# VCF-LM324-Stereo.net
KiCad netlist of a schematic drawn in EAGLE
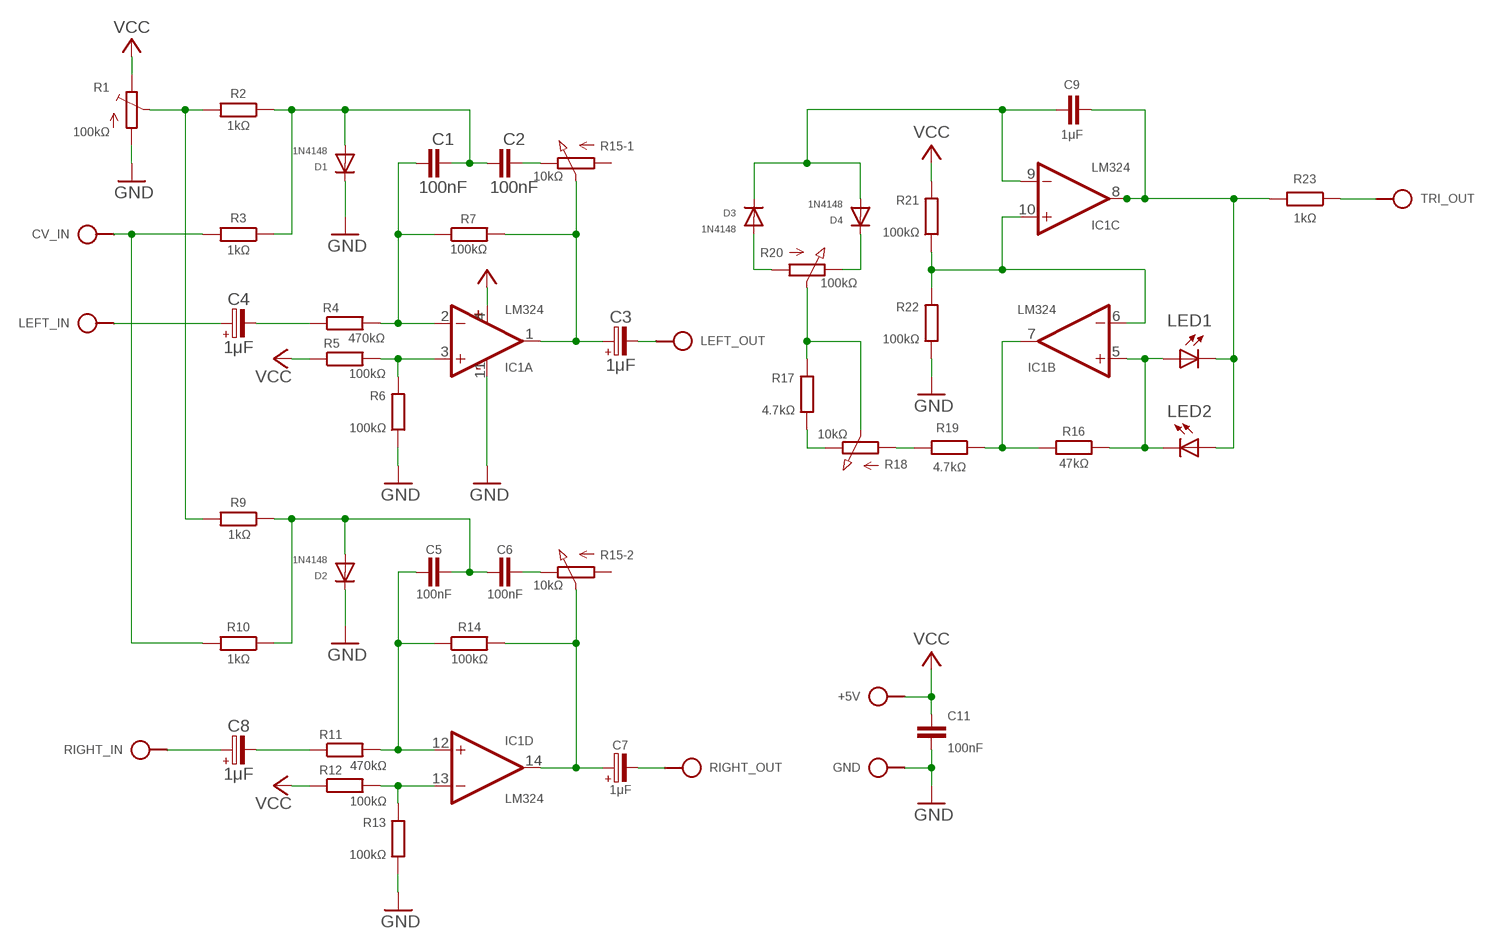
[diagram p0: schematic, sheet 1]

(export (version "E")
  (design (tool "Eeschema 10.0.6"))
  (components
    (comp (ref "+5V")
      (value "VCC")
      (footprint "eagle-import:SPAD")
      (libsource (lib "eagle-import") (part "SPAD"))
    )
    (comp (ref "C1")
      (value "100nF")
      (footprint "eagle-import:C050-024X044")
      (libsource (lib "eagle-import") (part "C050-024X044"))
    )
    (comp (ref "C2")
      (value "100nF")
      (footprint "eagle-import:C050-024X044")
      (libsource (lib "eagle-import") (part "C050-024X044"))
    )
    (comp (ref "C3")
      (value "1μF")
      (footprint "eagle-import:E2,5-3")
      (libsource (lib "eagle-import") (part "CPOLE2,5-3"))
    )
    (comp (ref "C4")
      (value "1μF")
      (footprint "eagle-import:E2,5-3")
      (libsource (lib "eagle-import") (part "CPOLE2,5-3"))
    )
    (comp (ref "C5")
      (value "100nF")
      (footprint "eagle-import:C050-024X044")
      (libsource (lib "eagle-import") (part "C050-024X044"))
    )
    (comp (ref "C6")
      (value "100nF")
      (footprint "eagle-import:C050-024X044")
      (libsource (lib "eagle-import") (part "C050-024X044"))
    )
    (comp (ref "C7")
      (value "1μF")
      (footprint "eagle-import:E2,5-3")
      (libsource (lib "eagle-import") (part "CPOLE2,5-3"))
    )
    (comp (ref "C8")
      (value "1μF")
      (footprint "eagle-import:E2,5-3")
      (libsource (lib "eagle-import") (part "CPOLE2,5-3"))
    )
    (comp (ref "C9")
      (value "1μF")
      (footprint "eagle-import:C050-024X044_V")
      (libsource (lib "eagle-import") (part "C050-024X044/V"))
    )
    (comp (ref "C11")
      (value "100nF")
      (footprint "eagle-import:C050-020X036")
      (libsource (lib "eagle-import") (part "C050-020X036"))
    )
    (comp (ref "CV_IN")
      (value "CV_IN")
      (footprint "eagle-import:SPAD")
      (libsource (lib "eagle-import") (part "SPAD"))
    )
    (comp (ref "D1")
      (value "1N4148")
      (footprint "eagle-import:DO34-10V")
      (libsource (lib "eagle-import") (part "1N414834-10V"))
    )
    (comp (ref "D2")
      (value "1N4148")
      (footprint "eagle-import:DO34-7V")
      (libsource (lib "eagle-import") (part "1N414834-7V"))
    )
    (comp (ref "D3")
      (value "1N4148")
      (footprint "eagle-import:DO34-7V")
      (libsource (lib "eagle-import") (part "1N414834-7V"))
    )
    (comp (ref "D4")
      (value "1N4148")
      (footprint "eagle-import:DO34-7V")
      (libsource (lib "eagle-import") (part "1N414834-7V"))
    )
    (comp (ref "GND")
      (value "GND")
      (footprint "eagle-import:SPAD")
      (libsource (lib "eagle-import") (part "SPAD"))
    )
    (comp (ref "IC1")
      (value "LM324")
      (footprint "eagle-import:DIL14")
      (libsource (lib "eagle-import") (part "LM324N"))
    )
    (comp (ref "LED1")
      (value "LED3MM")
      (footprint "eagle-import:LED3MM")
      (libsource (lib "eagle-import") (part "LED3MM"))
    )
    (comp (ref "LED2")
      (value "LED3MM")
      (footprint "eagle-import:LED3MM")
      (libsource (lib "eagle-import") (part "LED3MM"))
    )
    (comp (ref "LEFT_IN")
      (value "AUDIO_IN")
      (footprint "eagle-import:SPAD")
      (libsource (lib "eagle-import") (part "SPAD"))
    )
    (comp (ref "LEFT_OUT")
      (value "AUDIO_OUT")
      (footprint "eagle-import:SPAD")
      (libsource (lib "eagle-import") (part "SPAD"))
    )
    (comp (ref "R1")
      (value "100kΩ")
      (footprint "eagle-import:B64Y")
      (libsource (lib "eagle-import") (part "TRIM"))
    )
    (comp (ref "R2")
      (value "1kΩ")
      (footprint "eagle-import:0202_7")
      (libsource (lib "eagle-import") (part "R0202/7"))
    )
    (comp (ref "R3")
      (value "1kΩ")
      (footprint "eagle-import:0202_7")
      (libsource (lib "eagle-import") (part "R0202/7"))
    )
    (comp (ref "R4")
      (value "470kΩ")
      (footprint "eagle-import:0202_7")
      (libsource (lib "eagle-import") (part "R0202/7"))
    )
    (comp (ref "R5")
      (value "100kΩ")
      (footprint "eagle-import:0202_7")
      (libsource (lib "eagle-import") (part "R0202/7"))
    )
    (comp (ref "R6")
      (value "100kΩ")
      (footprint "eagle-import:0202_7")
      (libsource (lib "eagle-import") (part "R0202/7"))
    )
    (comp (ref "R7")
      (value "100kΩ")
      (footprint "eagle-import:0202_7")
      (libsource (lib "eagle-import") (part "R0202/7"))
    )
    (comp (ref "R9")
      (value "1kΩ")
      (footprint "eagle-import:0202_10")
      (libsource (lib "eagle-import") (part "R0202/10"))
    )
    (comp (ref "R10")
      (value "1kΩ")
      (footprint "eagle-import:0202_10")
      (libsource (lib "eagle-import") (part "R0202/10"))
    )
    (comp (ref "R11")
      (value "470kΩ")
      (footprint "eagle-import:0202_7")
      (libsource (lib "eagle-import") (part "R0202/7"))
    )
    (comp (ref "R12")
      (value "100kΩ")
      (footprint "eagle-import:0202_7")
      (libsource (lib "eagle-import") (part "R0202/7"))
    )
    (comp (ref "R13")
      (value "100kΩ")
      (footprint "eagle-import:0202_7")
      (libsource (lib "eagle-import") (part "R0202/7"))
    )
    (comp (ref "R14")
      (value "100kΩ")
      (footprint "eagle-import:0202_7")
      (libsource (lib "eagle-import") (part "R0202/7"))
    )
    (comp (ref "R15")
      (value "10kΩ")
      (footprint "eagle-import:POT-STEREO-2X3")
      (libsource (lib "eagle-import") (part "POT-STEREO"))
    )
    (comp (ref "R16")
      (value "47kΩ")
      (footprint "eagle-import:0202_7-V")
      (libsource (lib "eagle-import") (part "R0202/7-V"))
    )
    (comp (ref "R17")
      (value "4.7kΩ")
      (footprint "eagle-import:0202_7")
      (libsource (lib "eagle-import") (part "R0202/7"))
    )
    (comp (ref "R18")
      (value "10kΩ")
      (footprint "eagle-import:POT")
      (libsource (lib "eagle-import") (part "POT"))
    )
    (comp (ref "R19")
      (value "4.7kΩ")
      (footprint "eagle-import:0202_7-V")
      (libsource (lib "eagle-import") (part "R0202/7-V"))
    )
    (comp (ref "R20")
      (value "100kΩ")
      (footprint "eagle-import:POT")
      (libsource (lib "eagle-import") (part "POT"))
    )
    (comp (ref "R21")
      (value "100kΩ")
      (footprint "eagle-import:0202_7-V")
      (libsource (lib "eagle-import") (part "R0202/7-V"))
    )
    (comp (ref "R22")
      (value "100kΩ")
      (footprint "eagle-import:0202_7-V")
      (libsource (lib "eagle-import") (part "R0202/7-V"))
    )
    (comp (ref "R23")
      (value "1kΩ")
      (footprint "eagle-import:0202_7-V")
      (libsource (lib "eagle-import") (part "R0202/7-V"))
    )
    (comp (ref "RIGHT_IN")
      (value "AUDIO_IN")
      (footprint "eagle-import:SPAD")
      (libsource (lib "eagle-import") (part "SPAD"))
    )
    (comp (ref "RIGHT_OUT")
      (value "AUDIO_OUT")
      (footprint "eagle-import:SPAD")
      (libsource (lib "eagle-import") (part "SPAD"))
    )
    (comp (ref "TRI_OUT")
      (value "TRIANGLE")
      (footprint "eagle-import:SPAD")
      (libsource (lib "eagle-import") (part "SPAD"))
    )
  )
  (nets
    (net (code "1") (name "GND") (class "Default")
      (node (ref "C11") (pin "2") (pinfunction "2_2") (pintype "passive"))
      (node (ref "D1") (pin "C") (pinfunction "C_C") (pintype "passive"))
      (node (ref "D2") (pin "C") (pinfunction "C_C") (pintype "passive"))
      (node (ref "GND") (pin "1") (pinfunction "P$1_1") (pintype "bidirectional"))
      (node (ref "IC1") (pin "11") (pinfunction "V-_11") (pintype "power_in"))
      (node (ref "R1") (pin "A") (pinfunction "A_A") (pintype "passive"))
      (node (ref "R13") (pin "1") (pinfunction "1_1") (pintype "passive"))
      (node (ref "R22") (pin "1") (pinfunction "1_1") (pintype "passive"))
      (node (ref "R6") (pin "1") (pinfunction "1_1") (pintype "passive"))
    )
    (net (code "2") (name "Net-(C1-Pad2)") (class "Default")
      (node (ref "C1") (pin "2") (pinfunction "2_2") (pintype "passive"))
      (node (ref "C2") (pin "1") (pinfunction "1_1") (pintype "passive"))
      (node (ref "D1") (pin "A") (pinfunction "A_A") (pintype "passive"))
      (node (ref "R2") (pin "1") (pinfunction "1_1") (pintype "passive"))
      (node (ref "R3") (pin "1") (pinfunction "1_1") (pintype "passive"))
    )
    (net (code "3") (name "Net-(C4-Pad-)") (class "Default")
      (node (ref "C4") (pin "-") (pinfunction "-_-") (pintype "passive"))
      (node (ref "R4") (pin "1") (pinfunction "1_1") (pintype "passive"))
    )
    (net (code "4") (name "Net-(C5-Pad2)") (class "Default")
      (node (ref "C5") (pin "2") (pinfunction "2_2") (pintype "passive"))
      (node (ref "C6") (pin "1") (pinfunction "1_1") (pintype "passive"))
      (node (ref "D2") (pin "A") (pinfunction "A_A") (pintype "passive"))
      (node (ref "R10") (pin "1") (pinfunction "1_1") (pintype "passive"))
      (node (ref "R9") (pin "1") (pinfunction "1_1") (pintype "passive"))
    )
    (net (code "5") (name "Net-(C8-Pad-)") (class "Default")
      (node (ref "C8") (pin "-") (pinfunction "-_-") (pintype "passive"))
      (node (ref "R11") (pin "1") (pinfunction "1_1") (pintype "passive"))
    )
    (net (code "6") (name "Net-(CV_IN-P$1)") (class "Default")
      (node (ref "CV_IN") (pin "1") (pinfunction "P$1_1") (pintype "bidirectional"))
      (node (ref "R10") (pin "2") (pinfunction "2_2") (pintype "passive"))
      (node (ref "R3") (pin "2") (pinfunction "2_2") (pintype "passive"))
    )
    (net (code "7") (name "Net-(IC1A-+IN)") (class "Default")
      (node (ref "IC1") (pin "3") (pinfunction "+IN_3") (pintype "input"))
      (node (ref "R5") (pin "2") (pinfunction "2_2") (pintype "passive"))
      (node (ref "R6") (pin "2") (pinfunction "2_2") (pintype "passive"))
    )
    (net (code "8") (name "Net-(IC1A--IN)") (class "Default")
      (node (ref "C1") (pin "1") (pinfunction "1_1") (pintype "passive"))
      (node (ref "IC1") (pin "2") (pinfunction "-IN_2") (pintype "input"))
      (node (ref "R4") (pin "2") (pinfunction "2_2") (pintype "passive"))
      (node (ref "R7") (pin "1") (pinfunction "1_1") (pintype "passive"))
    )
    (net (code "9") (name "Net-(IC1A-OUT)") (class "Default")
      (node (ref "C3") (pin "+") (pinfunction "+_+") (pintype "passive"))
      (node (ref "IC1") (pin "1") (pinfunction "OUT_1") (pintype "output"))
      (node (ref "R15") (pin "1-S") (pinfunction "S_1-S") (pintype "passive"))
      (node (ref "R7") (pin "2") (pinfunction "2_2") (pintype "passive"))
    )
    (net (code "10") (name "Net-(IC1B-+IN)") (class "Default")
      (node (ref "IC1") (pin "5") (pinfunction "+IN_5") (pintype "input"))
      (node (ref "LED1") (pin "A") (pinfunction "A_A") (pintype "passive"))
      (node (ref "LED2") (pin "K") (pinfunction "C_K") (pintype "passive"))
      (node (ref "R16") (pin "1") (pinfunction "1_1") (pintype "passive"))
    )
    (net (code "11") (name "Net-(IC1B--IN)") (class "Default")
      (node (ref "IC1") (pin "10") (pinfunction "+IN_10") (pintype "input"))
      (node (ref "IC1") (pin "6") (pinfunction "-IN_6") (pintype "input"))
      (node (ref "R21") (pin "1") (pinfunction "1_1") (pintype "passive"))
      (node (ref "R22") (pin "2") (pinfunction "2_2") (pintype "passive"))
    )
    (net (code "12") (name "Net-(IC1B-OUT)") (class "Default")
      (node (ref "IC1") (pin "7") (pinfunction "OUT_7") (pintype "output"))
      (node (ref "R16") (pin "2") (pinfunction "2_2") (pintype "passive"))
      (node (ref "R19") (pin "1") (pinfunction "1_1") (pintype "passive"))
    )
    (net (code "13") (name "Net-(IC1C--IN)") (class "Default")
      (node (ref "C9") (pin "1") (pinfunction "1_1") (pintype "passive"))
      (node (ref "D3") (pin "C") (pinfunction "C_C") (pintype "passive"))
      (node (ref "D4") (pin "A") (pinfunction "A_A") (pintype "passive"))
      (node (ref "IC1") (pin "9") (pinfunction "-IN_9") (pintype "input"))
    )
    (net (code "14") (name "Net-(IC1C-OUT)") (class "Default")
      (node (ref "C9") (pin "2") (pinfunction "2_2") (pintype "passive"))
      (node (ref "IC1") (pin "8") (pinfunction "OUT_8") (pintype "output"))
      (node (ref "LED1") (pin "K") (pinfunction "C_K") (pintype "passive"))
      (node (ref "LED2") (pin "A") (pinfunction "A_A") (pintype "passive"))
      (node (ref "R23") (pin "2") (pinfunction "2_2") (pintype "passive"))
    )
    (net (code "15") (name "Net-(IC1D-+IN)") (class "Default")
      (node (ref "C5") (pin "1") (pinfunction "1_1") (pintype "passive"))
      (node (ref "IC1") (pin "12") (pinfunction "+IN_12") (pintype "input"))
      (node (ref "R11") (pin "2") (pinfunction "2_2") (pintype "passive"))
      (node (ref "R14") (pin "1") (pinfunction "1_1") (pintype "passive"))
    )
    (net (code "16") (name "Net-(IC1D--IN)") (class "Default")
      (node (ref "IC1") (pin "13") (pinfunction "-IN_13") (pintype "input"))
      (node (ref "R12") (pin "2") (pinfunction "2_2") (pintype "passive"))
      (node (ref "R13") (pin "2") (pinfunction "2_2") (pintype "passive"))
    )
    (net (code "17") (name "Net-(IC1D-OUT)") (class "Default")
      (node (ref "C7") (pin "+") (pinfunction "+_+") (pintype "passive"))
      (node (ref "IC1") (pin "14") (pinfunction "OUT_14") (pintype "output"))
      (node (ref "R14") (pin "2") (pinfunction "2_2") (pintype "passive"))
      (node (ref "R15") (pin "2-S") (pinfunction "S_2-S") (pintype "passive"))
    )
    (net (code "18") (name "Net-(LEFT_IN-P$1)") (class "Default")
      (node (ref "C4") (pin "+") (pinfunction "+_+") (pintype "passive"))
      (node (ref "LEFT_IN") (pin "1") (pinfunction "P$1_1") (pintype "bidirectional"))
    )
    (net (code "19") (name "Net-(LEFT_OUT-P$1)") (class "Default")
      (node (ref "C3") (pin "-") (pinfunction "-_-") (pintype "passive"))
      (node (ref "LEFT_OUT") (pin "1") (pinfunction "P$1_1") (pintype "bidirectional"))
    )
    (net (code "20") (name "Net-(R1-PadS)") (class "Default")
      (node (ref "R1") (pin "S") (pinfunction "S_S") (pintype "passive"))
      (node (ref "R2") (pin "2") (pinfunction "2_2") (pintype "passive"))
      (node (ref "R9") (pin "2") (pinfunction "2_2") (pintype "passive"))
    )
    (net (code "21") (name "Net-(R15A-E)") (class "Default")
      (node (ref "C2") (pin "2") (pinfunction "2_2") (pintype "passive"))
      (node (ref "R15") (pin "1-E") (pinfunction "E_1-E") (pintype "passive"))
    )
    (net (code "22") (name "Net-(R15B-E)") (class "Default")
      (node (ref "C6") (pin "2") (pinfunction "2_2") (pintype "passive"))
      (node (ref "R15") (pin "2-E") (pinfunction "E_2-E") (pintype "passive"))
    )
    (net (code "23") (name "Net-(R18-A)") (class "Default")
      (node (ref "R18") (pin "1") (pinfunction "A_1") (pintype "passive"))
      (node (ref "R19") (pin "2") (pinfunction "2_2") (pintype "passive"))
    )
    (net (code "24") (name "Net-(R18-E)") (class "Default")
      (node (ref "R17") (pin "1") (pinfunction "1_1") (pintype "passive"))
      (node (ref "R18") (pin "3") (pinfunction "E_3") (pintype "passive"))
    )
    (net (code "25") (name "Net-(R18-S)") (class "Default")
      (node (ref "R17") (pin "2") (pinfunction "2_2") (pintype "passive"))
      (node (ref "R18") (pin "2") (pinfunction "S_2") (pintype "passive"))
      (node (ref "R20") (pin "2") (pinfunction "S_2") (pintype "passive"))
    )
    (net (code "26") (name "Net-(R20-A)") (class "Default")
      (node (ref "D3") (pin "A") (pinfunction "A_A") (pintype "passive"))
      (node (ref "R20") (pin "1") (pinfunction "A_1") (pintype "passive"))
    )
    (net (code "27") (name "Net-(R20-E)") (class "Default")
      (node (ref "D4") (pin "C") (pinfunction "C_C") (pintype "passive"))
      (node (ref "R20") (pin "3") (pinfunction "E_3") (pintype "passive"))
    )
    (net (code "28") (name "Net-(RIGHT_IN-P$1)") (class "Default")
      (node (ref "C8") (pin "+") (pinfunction "+_+") (pintype "passive"))
      (node (ref "RIGHT_IN") (pin "1") (pinfunction "P$1_1") (pintype "bidirectional"))
    )
    (net (code "29") (name "Net-(RIGHT_OUT-P$1)") (class "Default")
      (node (ref "C7") (pin "-") (pinfunction "-_-") (pintype "passive"))
      (node (ref "RIGHT_OUT") (pin "1") (pinfunction "P$1_1") (pintype "bidirectional"))
    )
    (net (code "30") (name "Net-(TRI_OUT-P$1)") (class "Default")
      (node (ref "R23") (pin "1") (pinfunction "1_1") (pintype "passive"))
      (node (ref "TRI_OUT") (pin "1") (pinfunction "P$1_1") (pintype "bidirectional"))
    )
    (net (code "31") (name "VCC") (class "Default")
      (node (ref "+5V") (pin "1") (pinfunction "P$1_1") (pintype "bidirectional"))
      (node (ref "C11") (pin "1") (pinfunction "1_1") (pintype "passive"))
      (node (ref "IC1") (pin "4") (pinfunction "V+_4") (pintype "power_in"))
      (node (ref "R1") (pin "E") (pinfunction "E_E") (pintype "passive"))
      (node (ref "R12") (pin "1") (pinfunction "1_1") (pintype "passive"))
      (node (ref "R21") (pin "2") (pinfunction "2_2") (pintype "passive"))
      (node (ref "R5") (pin "1") (pinfunction "1_1") (pintype "passive"))
    )
    (net (code "32") (name "unconnected-(R15A-A-Pad1-A)") (class "Default")
      (node (ref "R15") (pin "1-A") (pinfunction "A_1-A") (pintype "passive"))
    )
    (net (code "33") (name "unconnected-(R15B-A-Pad2-A)") (class "Default")
      (node (ref "R15") (pin "2-A") (pinfunction "A_2-A") (pintype "passive"))
    )
  )
)
